# untitled.net
KiCad netlist of a schematic drawn in EAGLE
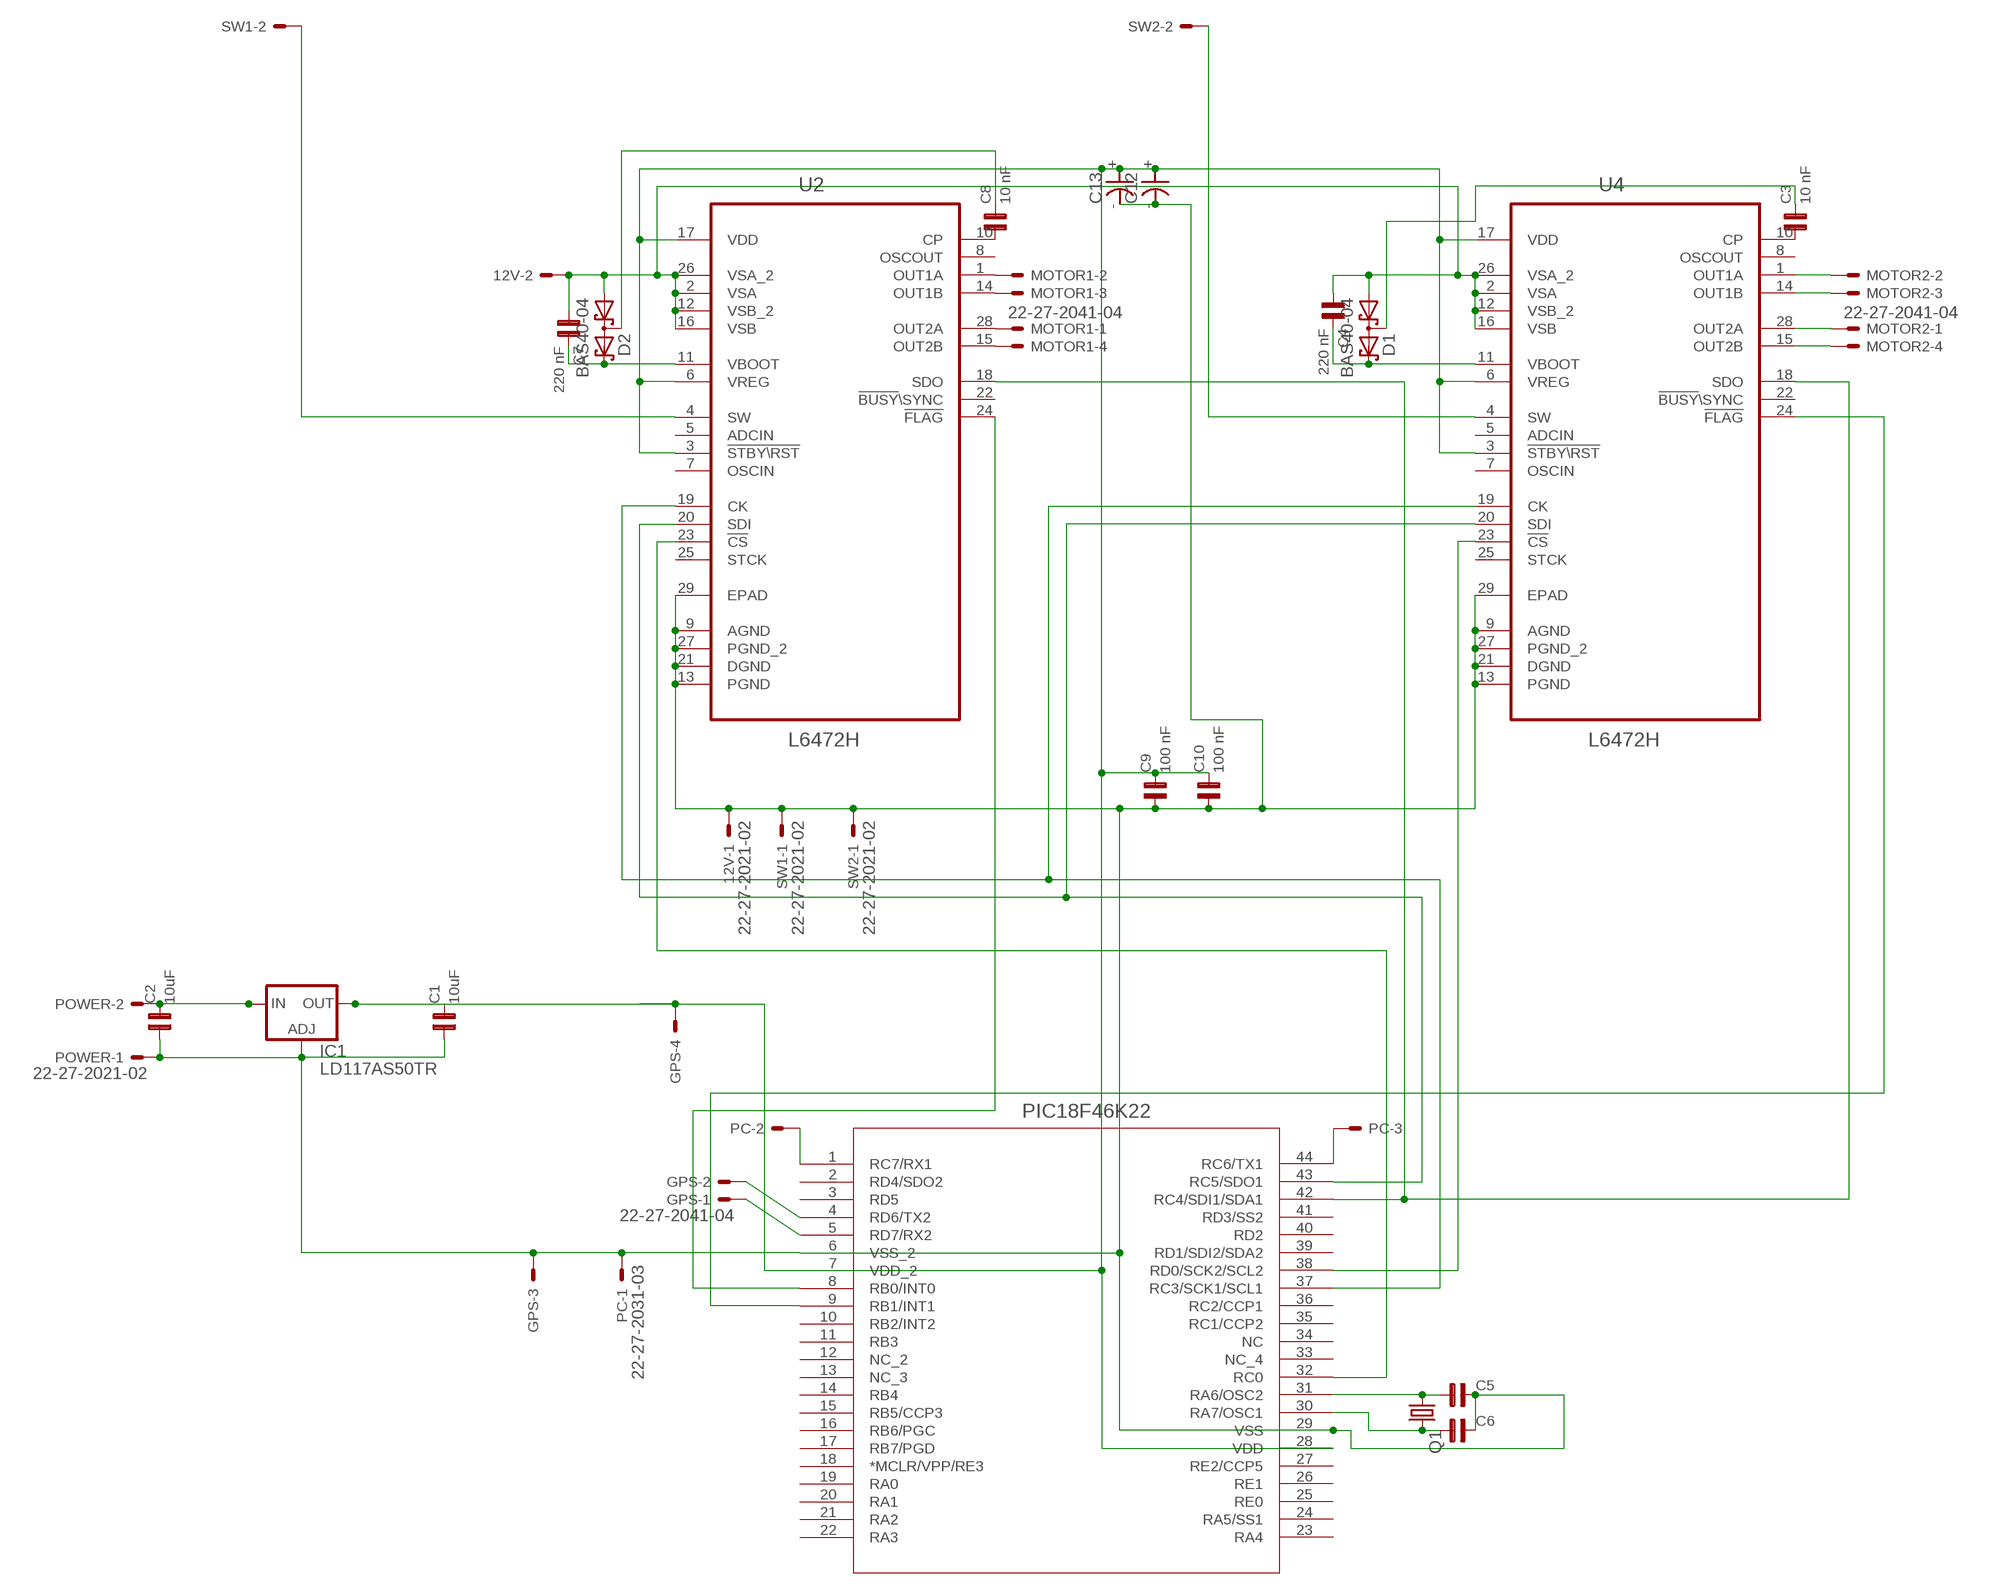
[diagram p0: schematic, sheet 1]

(export (version "E")
  (design (tool "Eeschema 10.0.6"))
  (components
    (comp (ref "12V")
      (value "22-27-2021-02")
      (footprint "eagle-import:6410-02")
      (libsource (lib "eagle-import") (part "22-?-0227-2021"))
    )
    (comp (ref "C1")
      (value "10uF")
      (footprint "eagle-import:0603")
      (libsource (lib "eagle-import") (part "C0603"))
    )
    (comp (ref "C2")
      (value "10uF")
      (footprint "eagle-import:0603")
      (libsource (lib "eagle-import") (part "C0603"))
    )
    (comp (ref "C3")
      (value "10 nF")
      (footprint "eagle-import:0603")
      (libsource (lib "eagle-import") (part "C0603"))
    )
    (comp (ref "C4")
      (value "220 nF")
      (footprint "eagle-import:0603")
      (libsource (lib "eagle-import") (part "C0603"))
    )
    (comp (ref "C5")
      (value "C0603")
      (footprint "eagle-import:0603")
      (libsource (lib "eagle-import") (part "C0603"))
    )
    (comp (ref "C6")
      (value "C0603")
      (footprint "eagle-import:0603")
      (libsource (lib "eagle-import") (part "C0603"))
    )
    (comp (ref "C7")
      (value "220 nF")
      (footprint "eagle-import:0603")
      (libsource (lib "eagle-import") (part "C0603"))
    )
    (comp (ref "C8")
      (value "10 nF")
      (footprint "eagle-import:0603")
      (libsource (lib "eagle-import") (part "C0603"))
    )
    (comp (ref "C9")
      (value "100 nF")
      (footprint "eagle-import:0603")
      (libsource (lib "eagle-import") (part "C0603"))
    )
    (comp (ref "C10")
      (value "100 nF")
      (footprint "eagle-import:0603")
      (libsource (lib "eagle-import") (part "C0603"))
    )
    (comp (ref "C12")
      (value "C7243")
      (footprint "eagle-import:7243")
      (libsource (lib "eagle-import") (part "C7243"))
    )
    (comp (ref "C13")
      (value "C7243")
      (footprint "eagle-import:7243")
      (libsource (lib "eagle-import") (part "C7243"))
    )
    (comp (ref "D1")
      (value "BAS40-04")
      (footprint "eagle-import:SOT23")
      (libsource (lib "eagle-import") (part "BAS40-04"))
    )
    (comp (ref "D2")
      (value "BAS40-04")
      (footprint "eagle-import:SOT23")
      (libsource (lib "eagle-import") (part "BAS40-04"))
    )
    (comp (ref "GPS")
      (value "22-27-2041-04")
      (footprint "eagle-import:6410-04")
      (libsource (lib "eagle-import") (part "22-?-0427-2041"))
    )
    (comp (ref "IC1")
      (value "LD117AS50TR")
      (footprint "eagle-import:SOT223")
      (libsource (lib "eagle-import") (part "LD117A?S50TR"))
    )
    (comp (ref "MOTOR1")
      (value "22-27-2041-04")
      (footprint "eagle-import:6410-04")
      (libsource (lib "eagle-import") (part "22-?-0427-2041"))
    )
    (comp (ref "MOTOR2")
      (value "22-27-2041-04")
      (footprint "eagle-import:6410-04")
      (libsource (lib "eagle-import") (part "22-?-0427-2041"))
    )
    (comp (ref "PC")
      (value "22-27-2031-03")
      (footprint "eagle-import:6410-03")
      (libsource (lib "eagle-import") (part "22-?-0327-2031"))
    )
    (comp (ref "POWER")
      (value "22-27-2021-02")
      (footprint "eagle-import:6410-02")
      (libsource (lib "eagle-import") (part "22-?-0227-2021"))
    )
    (comp (ref "Q1")
      (value "CRYSTALHC49S")
      (footprint "eagle-import:HC49_S")
      (libsource (lib "eagle-import") (part "CRYSTALHC49S"))
    )
    (comp (ref "SW1")
      (value "22-27-2021-02")
      (footprint "eagle-import:6410-02")
      (libsource (lib "eagle-import") (part "22-?-0227-2021"))
    )
    (comp (ref "SW2")
      (value "22-27-2021-02")
      (footprint "eagle-import:6410-02")
      (libsource (lib "eagle-import") (part "22-?-0227-2021"))
    )
    (comp (ref "U1")
      (value "PIC18F46K22-X_PT")
      (footprint "eagle-import:TQFP44_10X10MC")
      (libsource (lib "eagle-import") (part "PIC18F46K22-X_PT"))
    )
    (comp (ref "U2")
      (value "L6472H")
      (footprint "eagle-import:SOP65P640X120-29N")
      (libsource (lib "eagle-import") (part "L6472H"))
    )
    (comp (ref "U4")
      (value "L6472H")
      (footprint "eagle-import:SOP65P640X120-29N")
      (libsource (lib "eagle-import") (part "L6472H"))
    )
  )
  (nets
    (net (code "1") (name "Net-(12VA-S)") (class "Default")
      (node (ref "12V") (pin "1") (pinfunction "S_1") (pintype "passive"))
      (node (ref "C1") (pin "1") (pinfunction "1_1") (pintype "passive"))
      (node (ref "C10") (pin "1") (pinfunction "1_1") (pintype "passive"))
      (node (ref "C12") (pin "-") (pinfunction "-_-") (pintype "passive"))
      (node (ref "C13") (pin "-") (pinfunction "-_-") (pintype "passive"))
      (node (ref "C2") (pin "1") (pinfunction "1_1") (pintype "passive"))
      (node (ref "C5") (pin "2") (pinfunction "2_2") (pintype "passive"))
      (node (ref "C6") (pin "2") (pinfunction "2_2") (pintype "passive"))
      (node (ref "C9") (pin "1") (pinfunction "1_1") (pintype "passive"))
      (node (ref "GPS") (pin "3") (pinfunction "S_3") (pintype "passive"))
      (node (ref "IC1") (pin "1") (pinfunction "ADJ_1") (pintype "input"))
      (node (ref "PC") (pin "1") (pinfunction "S_1") (pintype "passive"))
      (node (ref "POWER") (pin "1") (pinfunction "S_1") (pintype "passive"))
      (node (ref "SW1") (pin "1") (pinfunction "S_1") (pintype "passive"))
      (node (ref "SW2") (pin "1") (pinfunction "S_1") (pintype "passive"))
      (node (ref "U1") (pin "29") (pinfunction "VSS_29") (pintype "passive"))
      (node (ref "U1") (pin "6") (pinfunction "VSS_2_6") (pintype "passive"))
      (node (ref "U2") (pin "13") (pinfunction "PGND_13") (pintype "passive"))
      (node (ref "U2") (pin "21") (pinfunction "DGND_21") (pintype "passive"))
      (node (ref "U2") (pin "27") (pinfunction "PGND_2_27") (pintype "passive"))
      (node (ref "U2") (pin "29") (pinfunction "EPAD_29") (pintype "passive"))
      (node (ref "U2") (pin "9") (pinfunction "AGND_9") (pintype "passive"))
      (node (ref "U4") (pin "13") (pinfunction "PGND_13") (pintype "passive"))
      (node (ref "U4") (pin "21") (pinfunction "DGND_21") (pintype "passive"))
      (node (ref "U4") (pin "27") (pinfunction "PGND_2_27") (pintype "passive"))
      (node (ref "U4") (pin "29") (pinfunction "EPAD_29") (pintype "passive"))
      (node (ref "U4") (pin "9") (pinfunction "AGND_9") (pintype "passive"))
    )
    (net (code "2") (name "Net-(12VB-S)") (class "Default")
      (node (ref "12V") (pin "2") (pinfunction "S_2") (pintype "passive"))
      (node (ref "C4") (pin "1") (pinfunction "1_1") (pintype "passive"))
      (node (ref "C7") (pin "1") (pinfunction "1_1") (pintype "passive"))
      (node (ref "D1") (pin "1") (pinfunction "A1_1") (pintype "passive"))
      (node (ref "D2") (pin "1") (pinfunction "A1_1") (pintype "passive"))
      (node (ref "U2") (pin "12") (pinfunction "VSB_2_12") (pintype "power_in"))
      (node (ref "U2") (pin "16") (pinfunction "VSB_16") (pintype "power_in"))
      (node (ref "U2") (pin "2") (pinfunction "VSA_2") (pintype "power_in"))
      (node (ref "U2") (pin "26") (pinfunction "VSA_2_26") (pintype "power_in"))
      (node (ref "U4") (pin "12") (pinfunction "VSB_2_12") (pintype "power_in"))
      (node (ref "U4") (pin "16") (pinfunction "VSB_16") (pintype "power_in"))
      (node (ref "U4") (pin "2") (pinfunction "VSA_2") (pintype "power_in"))
      (node (ref "U4") (pin "26") (pinfunction "VSA_2_26") (pintype "power_in"))
    )
    (net (code "3") (name "Net-(D1-C1A2)") (class "Default")
      (node (ref "C3") (pin "2") (pinfunction "2_2") (pintype "passive"))
      (node (ref "D1") (pin "3") (pinfunction "C1A2_3") (pintype "passive"))
    )
    (net (code "4") (name "Net-(D1-C2)") (class "Default")
      (node (ref "C4") (pin "2") (pinfunction "2_2") (pintype "passive"))
      (node (ref "D1") (pin "2") (pinfunction "C2_2") (pintype "passive"))
      (node (ref "U4") (pin "11") (pinfunction "VBOOT_11") (pintype "power_in"))
    )
    (net (code "5") (name "Net-(D2-C1A2)") (class "Default")
      (node (ref "C8") (pin "2") (pinfunction "2_2") (pintype "passive"))
      (node (ref "D2") (pin "3") (pinfunction "C1A2_3") (pintype "passive"))
    )
    (net (code "6") (name "Net-(D2-C2)") (class "Default")
      (node (ref "C7") (pin "2") (pinfunction "2_2") (pintype "passive"))
      (node (ref "D2") (pin "2") (pinfunction "C2_2") (pintype "passive"))
      (node (ref "U2") (pin "11") (pinfunction "VBOOT_11") (pintype "power_in"))
    )
    (net (code "7") (name "Net-(GPSA-S)") (class "Default")
      (node (ref "GPS") (pin "1") (pinfunction "S_1") (pintype "passive"))
      (node (ref "U1") (pin "5") (pinfunction "RD7/RX2_5") (pintype "passive"))
    )
    (net (code "8") (name "Net-(GPSB-S)") (class "Default")
      (node (ref "GPS") (pin "2") (pinfunction "S_2") (pintype "passive"))
      (node (ref "U1") (pin "4") (pinfunction "RD6/TX2_4") (pintype "passive"))
    )
    (net (code "9") (name "Net-(GPSD-S)") (class "Default")
      (node (ref "C1") (pin "2") (pinfunction "2_2") (pintype "passive"))
      (node (ref "C10") (pin "2") (pinfunction "2_2") (pintype "passive"))
      (node (ref "C12") (pin "+") (pinfunction "+_+") (pintype "passive"))
      (node (ref "C13") (pin "+") (pinfunction "+_+") (pintype "passive"))
      (node (ref "C9") (pin "2") (pinfunction "2_2") (pintype "passive"))
      (node (ref "GPS") (pin "4") (pinfunction "S_4") (pintype "passive"))
      (node (ref "IC1") (pin "4") (pinfunction "OUT_4") (pintype "passive"))
      (node (ref "U1") (pin "28") (pinfunction "VDD_28") (pintype "passive"))
      (node (ref "U1") (pin "7") (pinfunction "VDD_2_7") (pintype "passive"))
      (node (ref "U2") (pin "17") (pinfunction "VDD_17") (pintype "power_in"))
      (node (ref "U2") (pin "3") (pinfunction "~{STBY\\RST}_3") (pintype "input"))
      (node (ref "U2") (pin "6") (pinfunction "VREG_6") (pintype "power_in"))
      (node (ref "U4") (pin "17") (pinfunction "VDD_17") (pintype "power_in"))
      (node (ref "U4") (pin "3") (pinfunction "~{STBY\\RST}_3") (pintype "input"))
      (node (ref "U4") (pin "6") (pinfunction "VREG_6") (pintype "power_in"))
    )
    (net (code "10") (name "Net-(IC1-IN)") (class "Default")
      (node (ref "C2") (pin "2") (pinfunction "2_2") (pintype "passive"))
      (node (ref "IC1") (pin "3") (pinfunction "IN_3") (pintype "input"))
      (node (ref "POWER") (pin "2") (pinfunction "S_2") (pintype "passive"))
    )
    (net (code "11") (name "Net-(MOTOR1A-S)") (class "Default")
      (node (ref "MOTOR1") (pin "1") (pinfunction "S_1") (pintype "passive"))
      (node (ref "U2") (pin "28") (pinfunction "OUT2A_28") (pintype "output"))
    )
    (net (code "12") (name "Net-(MOTOR1B-S)") (class "Default")
      (node (ref "MOTOR1") (pin "2") (pinfunction "S_2") (pintype "passive"))
      (node (ref "U2") (pin "1") (pinfunction "OUT1A_1") (pintype "output"))
    )
    (net (code "13") (name "Net-(MOTOR1C-S)") (class "Default")
      (node (ref "MOTOR1") (pin "3") (pinfunction "S_3") (pintype "passive"))
      (node (ref "U2") (pin "14") (pinfunction "OUT1B_14") (pintype "output"))
    )
    (net (code "14") (name "Net-(MOTOR1D-S)") (class "Default")
      (node (ref "MOTOR1") (pin "4") (pinfunction "S_4") (pintype "passive"))
      (node (ref "U2") (pin "15") (pinfunction "OUT2B_15") (pintype "output"))
    )
    (net (code "15") (name "Net-(MOTOR2A-S)") (class "Default")
      (node (ref "MOTOR2") (pin "1") (pinfunction "S_1") (pintype "passive"))
      (node (ref "U4") (pin "28") (pinfunction "OUT2A_28") (pintype "output"))
    )
    (net (code "16") (name "Net-(MOTOR2B-S)") (class "Default")
      (node (ref "MOTOR2") (pin "2") (pinfunction "S_2") (pintype "passive"))
      (node (ref "U4") (pin "1") (pinfunction "OUT1A_1") (pintype "output"))
    )
    (net (code "17") (name "Net-(MOTOR2C-S)") (class "Default")
      (node (ref "MOTOR2") (pin "3") (pinfunction "S_3") (pintype "passive"))
      (node (ref "U4") (pin "14") (pinfunction "OUT1B_14") (pintype "output"))
    )
    (net (code "18") (name "Net-(MOTOR2D-S)") (class "Default")
      (node (ref "MOTOR2") (pin "4") (pinfunction "S_4") (pintype "passive"))
      (node (ref "U4") (pin "15") (pinfunction "OUT2B_15") (pintype "output"))
    )
    (net (code "19") (name "Net-(PCB-S)") (class "Default")
      (node (ref "PC") (pin "2") (pinfunction "S_2") (pintype "passive"))
      (node (ref "U1") (pin "1") (pinfunction "RC7/RX1_1") (pintype "passive"))
    )
    (net (code "20") (name "Net-(PCC-S)") (class "Default")
      (node (ref "PC") (pin "3") (pinfunction "S_3") (pintype "passive"))
      (node (ref "U1") (pin "44") (pinfunction "RC6/TX1_44") (pintype "passive"))
    )
    (net (code "21") (name "Net-(SW1B-S)") (class "Default")
      (node (ref "SW1") (pin "2") (pinfunction "S_2") (pintype "passive"))
      (node (ref "U2") (pin "4") (pinfunction "SW_4") (pintype "input"))
    )
    (net (code "22") (name "Net-(SW2B-S)") (class "Default")
      (node (ref "SW2") (pin "2") (pinfunction "S_2") (pintype "passive"))
      (node (ref "U4") (pin "4") (pinfunction "SW_4") (pintype "input"))
    )
    (net (code "23") (name "Net-(U1-RA6{slash}OSC2)") (class "Default")
      (node (ref "C5") (pin "1") (pinfunction "1_1") (pintype "passive"))
      (node (ref "Q1") (pin "1") (pinfunction "1_1") (pintype "passive"))
      (node (ref "U1") (pin "31") (pinfunction "RA6/OSC2_31") (pintype "passive"))
    )
    (net (code "24") (name "Net-(U1-RA7{slash}OSC1)") (class "Default")
      (node (ref "C6") (pin "1") (pinfunction "1_1") (pintype "passive"))
      (node (ref "Q1") (pin "2") (pinfunction "2_2") (pintype "passive"))
      (node (ref "U1") (pin "30") (pinfunction "RA7/OSC1_30") (pintype "passive"))
    )
    (net (code "25") (name "Net-(U1-RB0{slash}INT0)") (class "Default")
      (node (ref "U1") (pin "8") (pinfunction "RB0/INT0_8") (pintype "passive"))
      (node (ref "U2") (pin "24") (pinfunction "~{FLAG}_24") (pintype "output"))
    )
    (net (code "26") (name "Net-(U1-RB1{slash}INT1)") (class "Default")
      (node (ref "U1") (pin "9") (pinfunction "RB1/INT1_9") (pintype "passive"))
      (node (ref "U4") (pin "24") (pinfunction "~{FLAG}_24") (pintype "output"))
    )
    (net (code "27") (name "Net-(U1-RC0)") (class "Default")
      (node (ref "U1") (pin "32") (pinfunction "RC0_32") (pintype "passive"))
      (node (ref "U2") (pin "23") (pinfunction "~{CS}_23") (pintype "input"))
    )
    (net (code "28") (name "Net-(U1-RC3{slash}SCK1{slash}SCL1)") (class "Default")
      (node (ref "U1") (pin "37") (pinfunction "RC3/SCK1/SCL1_37") (pintype "passive"))
      (node (ref "U2") (pin "19") (pinfunction "CK_19") (pintype "input"))
      (node (ref "U4") (pin "19") (pinfunction "CK_19") (pintype "input"))
    )
    (net (code "29") (name "Net-(U1-RC4{slash}SDI1{slash}SDA1)") (class "Default")
      (node (ref "U1") (pin "42") (pinfunction "RC4/SDI1/SDA1_42") (pintype "passive"))
      (node (ref "U2") (pin "18") (pinfunction "SDO_18") (pintype "output"))
      (node (ref "U4") (pin "18") (pinfunction "SDO_18") (pintype "output"))
    )
    (net (code "30") (name "Net-(U1-RC5{slash}SDO1)") (class "Default")
      (node (ref "U1") (pin "43") (pinfunction "RC5/SDO1_43") (pintype "passive"))
      (node (ref "U2") (pin "20") (pinfunction "SDI_20") (pintype "input"))
      (node (ref "U4") (pin "20") (pinfunction "SDI_20") (pintype "input"))
    )
    (net (code "31") (name "Net-(U1-RD0{slash}SCK2{slash}SCL2)") (class "Default")
      (node (ref "U1") (pin "38") (pinfunction "RD0/SCK2/SCL2_38") (pintype "passive"))
      (node (ref "U4") (pin "23") (pinfunction "~{CS}_23") (pintype "input"))
    )
    (net (code "32") (name "Net-(U2-CP)") (class "Default")
      (node (ref "C8") (pin "1") (pinfunction "1_1") (pintype "passive"))
      (node (ref "U2") (pin "10") (pinfunction "CP_10") (pintype "output"))
    )
    (net (code "33") (name "Net-(U4-CP)") (class "Default")
      (node (ref "C3") (pin "1") (pinfunction "1_1") (pintype "passive"))
      (node (ref "U4") (pin "10") (pinfunction "CP_10") (pintype "output"))
    )
    (net (code "34") (name "unconnected-(U1-*MCLR{slash}VPP{slash}RE3-Pad18)") (class "Default")
      (node (ref "U1") (pin "18") (pinfunction "*MCLR/VPP/RE3_18") (pintype "passive"))
    )
    (net (code "35") (name "unconnected-(U1-NC-Pad34)") (class "Default")
      (node (ref "U1") (pin "34") (pinfunction "NC_34") (pintype "passive"))
    )
    (net (code "36") (name "unconnected-(U1-NC_2-Pad12)") (class "Default")
      (node (ref "U1") (pin "12") (pinfunction "NC_2_12") (pintype "passive"))
    )
    (net (code "37") (name "unconnected-(U1-NC_3-Pad13)") (class "Default")
      (node (ref "U1") (pin "13") (pinfunction "NC_3_13") (pintype "passive"))
    )
    (net (code "38") (name "unconnected-(U1-NC_4-Pad33)") (class "Default")
      (node (ref "U1") (pin "33") (pinfunction "NC_4_33") (pintype "passive"))
    )
    (net (code "39") (name "unconnected-(U1-RA0-Pad19)") (class "Default")
      (node (ref "U1") (pin "19") (pinfunction "RA0_19") (pintype "passive"))
    )
    (net (code "40") (name "unconnected-(U1-RA1-Pad20)") (class "Default")
      (node (ref "U1") (pin "20") (pinfunction "RA1_20") (pintype "passive"))
    )
    (net (code "41") (name "unconnected-(U1-RA2-Pad21)") (class "Default")
      (node (ref "U1") (pin "21") (pinfunction "RA2_21") (pintype "passive"))
    )
    (net (code "42") (name "unconnected-(U1-RA3-Pad22)") (class "Default")
      (node (ref "U1") (pin "22") (pinfunction "RA3_22") (pintype "passive"))
    )
    (net (code "43") (name "unconnected-(U1-RA4-Pad23)") (class "Default")
      (node (ref "U1") (pin "23") (pinfunction "RA4_23") (pintype "passive"))
    )
    (net (code "44") (name "unconnected-(U1-RA5{slash}SS1-Pad24)") (class "Default")
      (node (ref "U1") (pin "24") (pinfunction "RA5/SS1_24") (pintype "passive"))
    )
    (net (code "45") (name "unconnected-(U1-RB2{slash}INT2-Pad10)") (class "Default")
      (node (ref "U1") (pin "10") (pinfunction "RB2/INT2_10") (pintype "passive"))
    )
    (net (code "46") (name "unconnected-(U1-RB3-Pad11)") (class "Default")
      (node (ref "U1") (pin "11") (pinfunction "RB3_11") (pintype "passive"))
    )
    (net (code "47") (name "unconnected-(U1-RB4-Pad14)") (class "Default")
      (node (ref "U1") (pin "14") (pinfunction "RB4_14") (pintype "passive"))
    )
    (net (code "48") (name "unconnected-(U1-RB5{slash}CCP3-Pad15)") (class "Default")
      (node (ref "U1") (pin "15") (pinfunction "RB5/CCP3_15") (pintype "passive"))
    )
    (net (code "49") (name "unconnected-(U1-RB6{slash}PGC-Pad16)") (class "Default")
      (node (ref "U1") (pin "16") (pinfunction "RB6/PGC_16") (pintype "passive"))
    )
    (net (code "50") (name "unconnected-(U1-RB7{slash}PGD-Pad17)") (class "Default")
      (node (ref "U1") (pin "17") (pinfunction "RB7/PGD_17") (pintype "passive"))
    )
    (net (code "51") (name "unconnected-(U1-RC1{slash}CCP2-Pad35)") (class "Default")
      (node (ref "U1") (pin "35") (pinfunction "RC1/CCP2_35") (pintype "passive"))
    )
    (net (code "52") (name "unconnected-(U1-RC2{slash}CCP1-Pad36)") (class "Default")
      (node (ref "U1") (pin "36") (pinfunction "RC2/CCP1_36") (pintype "passive"))
    )
    (net (code "53") (name "unconnected-(U1-RD1{slash}SDI2{slash}SDA2-Pad39)") (class "Default")
      (node (ref "U1") (pin "39") (pinfunction "RD1/SDI2/SDA2_39") (pintype "passive"))
    )
    (net (code "54") (name "unconnected-(U1-RD2-Pad40)") (class "Default")
      (node (ref "U1") (pin "40") (pinfunction "RD2_40") (pintype "passive"))
    )
    (net (code "55") (name "unconnected-(U1-RD3{slash}SS2-Pad41)") (class "Default")
      (node (ref "U1") (pin "41") (pinfunction "RD3/SS2_41") (pintype "passive"))
    )
    (net (code "56") (name "unconnected-(U1-RD4{slash}SDO2-Pad2)") (class "Default")
      (node (ref "U1") (pin "2") (pinfunction "RD4/SDO2_2") (pintype "passive"))
    )
    (net (code "57") (name "unconnected-(U1-RD5-Pad3)") (class "Default")
      (node (ref "U1") (pin "3") (pinfunction "RD5_3") (pintype "passive"))
    )
    (net (code "58") (name "unconnected-(U1-RE0-Pad25)") (class "Default")
      (node (ref "U1") (pin "25") (pinfunction "RE0_25") (pintype "passive"))
    )
    (net (code "59") (name "unconnected-(U1-RE1-Pad26)") (class "Default")
      (node (ref "U1") (pin "26") (pinfunction "RE1_26") (pintype "passive"))
    )
    (net (code "60") (name "unconnected-(U1-RE2{slash}CCP5-Pad27)") (class "Default")
      (node (ref "U1") (pin "27") (pinfunction "RE2/CCP5_27") (pintype "passive"))
    )
    (net (code "61") (name "unconnected-(U2-ADCIN-Pad5)") (class "Default")
      (node (ref "U2") (pin "5") (pinfunction "ADCIN_5") (pintype "input"))
    )
    (net (code "62") (name "unconnected-(U2-OSCIN-Pad7)") (class "Default")
      (node (ref "U2") (pin "7") (pinfunction "OSCIN_7") (pintype "input"))
    )
    (net (code "63") (name "unconnected-(U2-OSCOUT-Pad8)") (class "Default")
      (node (ref "U2") (pin "8") (pinfunction "OSCOUT_8") (pintype "output"))
    )
    (net (code "64") (name "unconnected-(U2-STCK-Pad25)") (class "Default")
      (node (ref "U2") (pin "25") (pinfunction "STCK_25") (pintype "input"))
    )
    (net (code "65") (name "unconnected-(U2-~{BUSY}\\SYNC-Pad22)") (class "Default")
      (node (ref "U2") (pin "22") (pinfunction "~{BUSY}\\SYNC_22") (pintype "output"))
    )
    (net (code "66") (name "unconnected-(U4-ADCIN-Pad5)") (class "Default")
      (node (ref "U4") (pin "5") (pinfunction "ADCIN_5") (pintype "input"))
    )
    (net (code "67") (name "unconnected-(U4-OSCIN-Pad7)") (class "Default")
      (node (ref "U4") (pin "7") (pinfunction "OSCIN_7") (pintype "input"))
    )
    (net (code "68") (name "unconnected-(U4-OSCOUT-Pad8)") (class "Default")
      (node (ref "U4") (pin "8") (pinfunction "OSCOUT_8") (pintype "output"))
    )
    (net (code "69") (name "unconnected-(U4-STCK-Pad25)") (class "Default")
      (node (ref "U4") (pin "25") (pinfunction "STCK_25") (pintype "input"))
    )
    (net (code "70") (name "unconnected-(U4-~{BUSY}\\SYNC-Pad22)") (class "Default")
      (node (ref "U4") (pin "22") (pinfunction "~{BUSY}\\SYNC_22") (pintype "output"))
    )
  )
)
